# 14_LCD_Power_Supply.net
KiCad netlist of a schematic drawn in Altium Designer
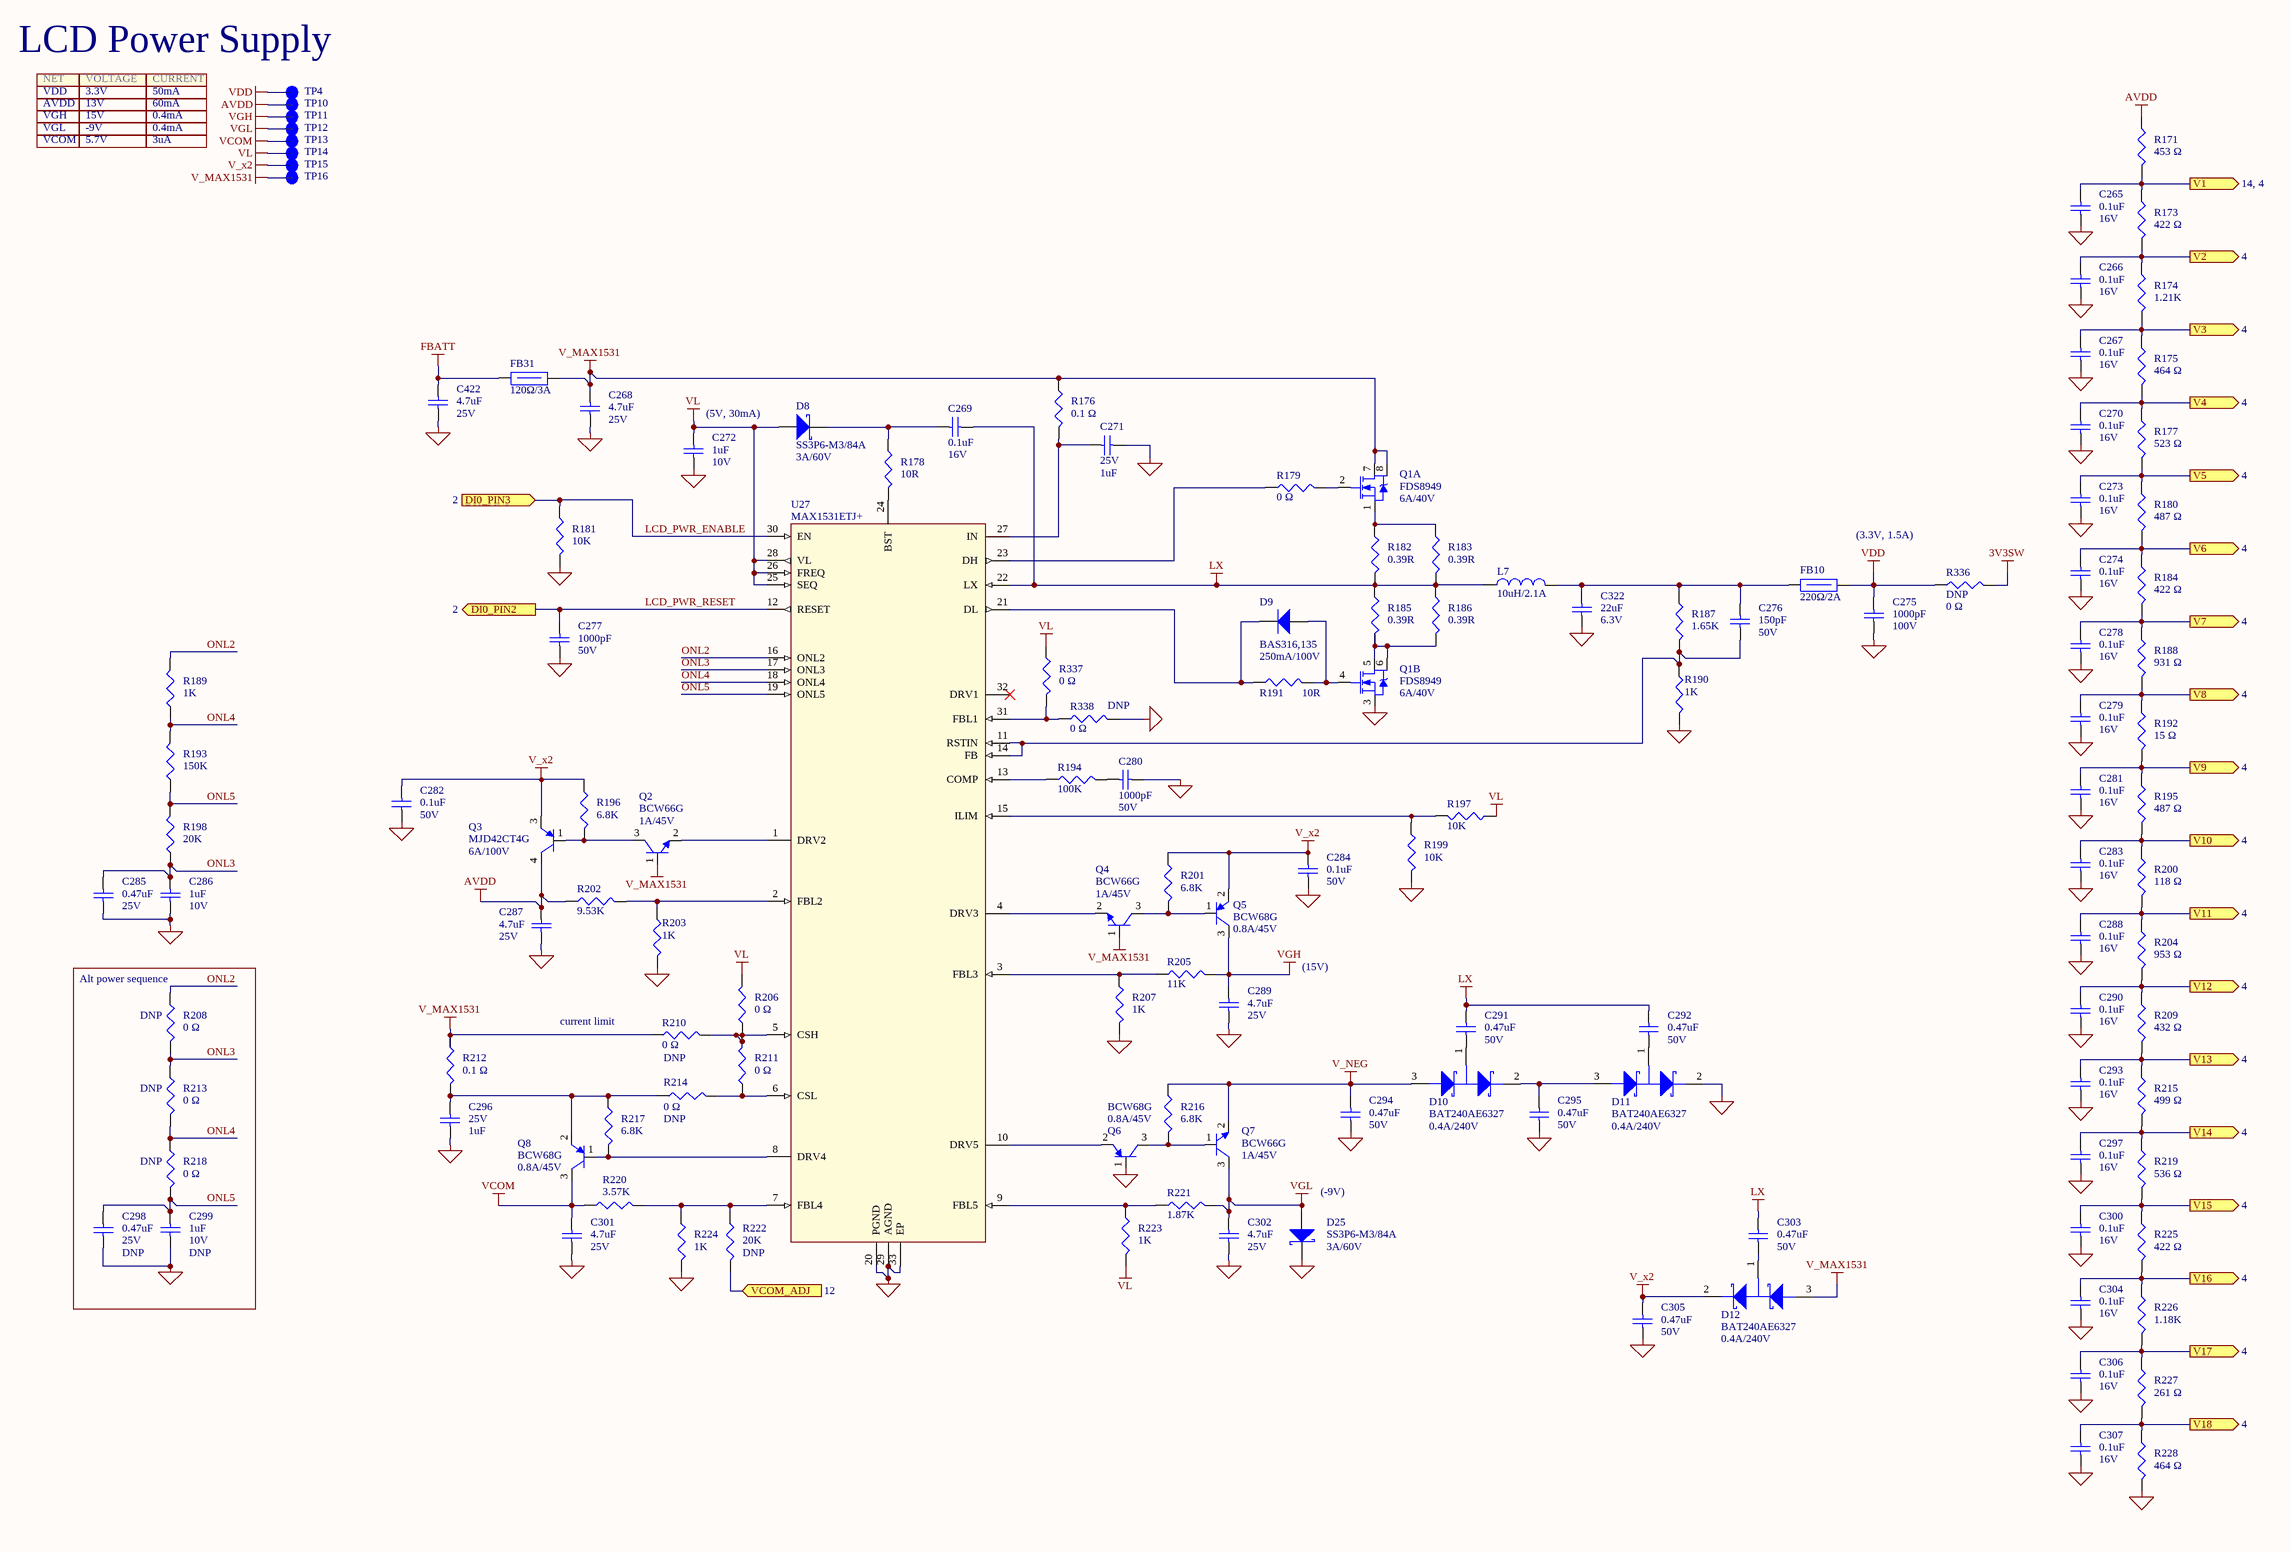
[diagram p0: 14 LCD Power Supply.SchDoc]

(export (version "E")
  (design (tool "Eeschema 10.0.6"))
  (components
    (comp (ref "C265")
      (value "0.1uF")
      (footprint "CAP_0402")
      (description "Cap, Cer, 0.1uF, 16V, 10%, X7R, 0402")
      (fields
        (field (name "TOLERANCE") "±10%")
        (field (name "MANUFACTURER") "Murata Electronics North America")
        (field (name "VOLTAGE") "16V")
      )
      (libsource (lib "Firstview") (part "Cap 0.1uF 16V 0402"))
    )
    (comp (ref "C266")
      (value "0.1uF")
      (footprint "CAP_0402")
      (description "Cap, Cer, 0.1uF, 16V, 10%, X7R, 0402")
      (fields
        (field (name "TOLERANCE") "±10%")
        (field (name "MANUFACTURER") "Murata Electronics North America")
        (field (name "VOLTAGE") "16V")
      )
      (libsource (lib "Firstview") (part "Cap 0.1uF 16V 0402"))
    )
    (comp (ref "C267")
      (value "0.1uF")
      (footprint "CAP_0402")
      (description "Cap, Cer, 0.1uF, 16V, 10%, X7R, 0402")
      (fields
        (field (name "TOLERANCE") "±10%")
        (field (name "MANUFACTURER") "Murata Electronics North America")
        (field (name "VOLTAGE") "16V")
      )
      (libsource (lib "Firstview") (part "Cap 0.1uF 16V 0402"))
    )
    (comp (ref "C268")
      (value "4.7uF")
      (footprint "CAP_0805")
      (description "Cap, Cer, 4.7uF, 25V, 10%, X5R, 0805")
      (fields
        (field (name "TOLERANCE") "10%")
        (field (name "MANUFACTURER") "Murata Electronics North America")
        (field (name "VOLTAGE") "25V")
      )
      (libsource (lib "Firstview") (part "Cap 4.7uF 25V 0805"))
    )
    (comp (ref "C269")
      (value "0.1uF")
      (footprint "CAP_0402")
      (description "Cap, Cer, 0.1uF, 16V, 10%, X7R, 0402")
      (fields
        (field (name "TOLERANCE") "±10%")
        (field (name "MANUFACTURER") "Murata Electronics North America")
        (field (name "VOLTAGE") "16V")
      )
      (libsource (lib "Firstview") (part "Cap 0.1uF 16V 0402"))
    )
    (comp (ref "C270")
      (value "0.1uF")
      (footprint "CAP_0402")
      (description "Cap, Cer, 0.1uF, 16V, 10%, X7R, 0402")
      (fields
        (field (name "TOLERANCE") "±10%")
        (field (name "MANUFACTURER") "Murata Electronics North America")
        (field (name "VOLTAGE") "16V")
      )
      (libsource (lib "Firstview") (part "Cap 0.1uF 16V 0402"))
    )
    (comp (ref "C271")
      (value "1uF")
      (footprint "CAP_0402")
      (description "Cap, Cer, 1uF, 25V, 10%, X5R, 0402")
      (fields
        (field (name "VOLTAGE") "25V")
        (field (name "MANUFACTURER") "Taiyo Yuden")
        (field (name "Comment") "Cap 1uF 25V 0402")
      )
      (libsource (lib "Firstview") (part "Cap 1uF 25V 0402"))
    )
    (comp (ref "C272")
      (value "1uF")
      (footprint "CAP_0402")
      (description "Cap, Cer, 1uF, 10V, ±10%, X5R, 0402")
      (fields
        (field (name "VOLTAGE") "10V")
        (field (name "MANUFACTURER") "Yageo")
        (field (name "Comment") "Cap 1uF 10V 0402")
      )
      (libsource (lib "Firstview") (part "Cap 1uF 10V 0402"))
    )
    (comp (ref "C273")
      (value "0.1uF")
      (footprint "CAP_0402")
      (description "Cap, Cer, 0.1uF, 16V, 10%, X7R, 0402")
      (fields
        (field (name "TOLERANCE") "±10%")
        (field (name "MANUFACTURER") "Murata Electronics North America")
        (field (name "VOLTAGE") "16V")
      )
      (libsource (lib "Firstview") (part "Cap 0.1uF 16V 0402"))
    )
    (comp (ref "C274")
      (value "0.1uF")
      (footprint "CAP_0402")
      (description "Cap, Cer, 0.1uF, 16V, 10%, X7R, 0402")
      (fields
        (field (name "TOLERANCE") "±10%")
        (field (name "MANUFACTURER") "Murata Electronics North America")
        (field (name "VOLTAGE") "16V")
      )
      (libsource (lib "Firstview") (part "Cap 0.1uF 16V 0402"))
    )
    (comp (ref "C275")
      (value "1000pF")
      (footprint "CAP_0402")
      (description "Cap, Cer, 1000pF, 100V, 20%, X7S, 0402")
      (fields
        (field (name "TOLERANCE") "20%")
        (field (name "MANUFACTURER") "TDK Corporation")
        (field (name "VOLTAGE") "100V")
      )
      (libsource (lib "Firstview") (part "Cap 1000pF 100V 0402"))
    )
    (comp (ref "C276")
      (value "150pF")
      (footprint "CAP_0402")
      (description "Cap, Cer, 150pF, 50V, 5%, C0G/NP0, 0603")
      (fields
        (field (name "TOLERANCE") "5%")
        (field (name "MANUFACTURER") "Samsung Electro-Mechanics America, Inc")
        (field (name "VOLTAGE") "50V")
      )
      (libsource (lib "Firstview") (part "Cap 150pF 50V 0603"))
    )
    (comp (ref "C277")
      (value "1000pF")
      (footprint "CAP_0603")
      (description "Cap, Cer, 1000pF, 50V, 10%, X7S, 0603")
      (fields
        (field (name "TOLERANCE") "10%")
        (field (name "MANUFACTURER") "Yageo")
        (field (name "VOLTAGE") "50V")
      )
      (libsource (lib "Firstview") (part "Cap 1000pF 50V 0603"))
    )
    (comp (ref "C278")
      (value "0.1uF")
      (footprint "CAP_0402")
      (description "Cap, Cer, 0.1uF, 16V, 10%, X7R, 0402")
      (fields
        (field (name "TOLERANCE") "±10%")
        (field (name "MANUFACTURER") "Murata Electronics North America")
        (field (name "VOLTAGE") "16V")
      )
      (libsource (lib "Firstview") (part "Cap 0.1uF 16V 0402"))
    )
    (comp (ref "C279")
      (value "0.1uF")
      (footprint "CAP_0402")
      (description "Cap, Cer, 0.1uF, 16V, 10%, X7R, 0402")
      (fields
        (field (name "TOLERANCE") "±10%")
        (field (name "MANUFACTURER") "Murata Electronics North America")
        (field (name "VOLTAGE") "16V")
      )
      (libsource (lib "Firstview") (part "Cap 0.1uF 16V 0402"))
    )
    (comp (ref "C280")
      (value "1000pF")
      (footprint "CAP_0603")
      (description "Cap, Cer, 1000pF, 50V, 10%, X7S, 0603")
      (fields
        (field (name "TOLERANCE") "10%")
        (field (name "MANUFACTURER") "Yageo")
        (field (name "VOLTAGE") "50V")
      )
      (libsource (lib "Firstview") (part "Cap 1000pF 50V 0603"))
    )
    (comp (ref "C281")
      (value "0.1uF")
      (footprint "CAP_0402")
      (description "Cap, Cer, 0.1uF, 16V, 10%, X7R, 0402")
      (fields
        (field (name "TOLERANCE") "±10%")
        (field (name "MANUFACTURER") "Murata Electronics North America")
        (field (name "VOLTAGE") "16V")
      )
      (libsource (lib "Firstview") (part "Cap 0.1uF 16V 0402"))
    )
    (comp (ref "C282")
      (value "0.1uF")
      (footprint "CAP_0402")
      (description "Cap, Cer, 0.1uF, 50V, 10%, X5R, 0402")
      (fields
        (field (name "TOLERANCE") "±10%")
        (field (name "MANUFACTURER") "TDK Corporation")
        (field (name "VOLTAGE") "50V")
      )
      (libsource (lib "Firstview") (part "Cap 0.1uF 50V 0402"))
    )
    (comp (ref "C283")
      (value "0.1uF")
      (footprint "CAP_0402")
      (description "Cap, Cer, 0.1uF, 16V, 10%, X7R, 0402")
      (fields
        (field (name "TOLERANCE") "±10%")
        (field (name "MANUFACTURER") "Murata Electronics North America")
        (field (name "VOLTAGE") "16V")
      )
      (libsource (lib "Firstview") (part "Cap 0.1uF 16V 0402"))
    )
    (comp (ref "C284")
      (value "0.1uF")
      (footprint "CAP_0402")
      (description "Cap, Cer, 0.1uF, 50V, 10%, X5R, 0402")
      (fields
        (field (name "TOLERANCE") "±10%")
        (field (name "MANUFACTURER") "TDK Corporation")
        (field (name "VOLTAGE") "50V")
      )
      (libsource (lib "Firstview") (part "Cap 0.1uF 50V 0402"))
    )
    (comp (ref "C285")
      (value "0.47uF")
      (footprint "CAP_0603")
      (description "Cap, Cer, 0.47uF, 25V, 10%, X7R, 0603")
      (fields
        (field (name "MANUFACTURER") "Samsung Electro-Mechanics America, Inc")
        (field (name "TOLERANCE") "10%")
        (field (name "VOLTAGE") "25V")
      )
      (libsource (lib "Firstview") (part "Cap 0.47uF 25V 0603"))
    )
    (comp (ref "C286")
      (value "1uF")
      (footprint "CAP_0402")
      (description "Cap, Cer, 1uF, 10V, ±10%, X5R, 0402")
      (fields
        (field (name "VOLTAGE") "10V")
        (field (name "MANUFACTURER") "Yageo")
        (field (name "Comment") "Cap 1uF 10V 0402")
      )
      (libsource (lib "Firstview") (part "Cap 1uF 10V 0402"))
    )
    (comp (ref "C287")
      (value "4.7uF")
      (footprint "CAP_0805")
      (description "Cap, Cer, 4.7uF, 25V, 10%, X5R, 0805")
      (fields
        (field (name "TOLERANCE") "10%")
        (field (name "MANUFACTURER") "Murata Electronics North America")
        (field (name "VOLTAGE") "25V")
      )
      (libsource (lib "Firstview") (part "Cap 4.7uF 25V 0805"))
    )
    (comp (ref "C288")
      (value "0.1uF")
      (footprint "CAP_0402")
      (description "Cap, Cer, 0.1uF, 16V, 10%, X7R, 0402")
      (fields
        (field (name "TOLERANCE") "±10%")
        (field (name "MANUFACTURER") "Murata Electronics North America")
        (field (name "VOLTAGE") "16V")
      )
      (libsource (lib "Firstview") (part "Cap 0.1uF 16V 0402"))
    )
    (comp (ref "C289")
      (value "4.7uF")
      (footprint "CAP_0805")
      (description "Cap, Cer, 4.7uF, 25V, 10%, X5R, 0805")
      (fields
        (field (name "TOLERANCE") "10%")
        (field (name "MANUFACTURER") "Murata Electronics North America")
        (field (name "VOLTAGE") "25V")
      )
      (libsource (lib "Firstview") (part "Cap 4.7uF 25V 0805"))
    )
    (comp (ref "C290")
      (value "0.1uF")
      (footprint "CAP_0402")
      (description "Cap, Cer, 0.1uF, 16V, 10%, X7R, 0402")
      (fields
        (field (name "TOLERANCE") "±10%")
        (field (name "MANUFACTURER") "Murata Electronics North America")
        (field (name "VOLTAGE") "16V")
      )
      (libsource (lib "Firstview") (part "Cap 0.1uF 16V 0402"))
    )
    (comp (ref "C291")
      (value "0.47uF")
      (footprint "CAP_1206")
      (description "Cap, Cer, 0.47uF, 50V, 10%, X7R, 1206")
      (fields
        (field (name "MANUFACTURER") "Yageo")
        (field (name "TOLERANCE") "10%")
        (field (name "VOLTAGE") "50V")
      )
      (libsource (lib "Firstview") (part "Cap 0.47uF 50V 1206"))
    )
    (comp (ref "C292")
      (value "0.47uF")
      (footprint "CAP_1206")
      (description "Cap, Cer, 0.47uF, 50V, 10%, X7R, 1206")
      (fields
        (field (name "MANUFACTURER") "Yageo")
        (field (name "TOLERANCE") "10%")
        (field (name "VOLTAGE") "50V")
      )
      (libsource (lib "Firstview") (part "Cap 0.47uF 50V 1206"))
    )
    (comp (ref "C293")
      (value "0.1uF")
      (footprint "CAP_0402")
      (description "Cap, Cer, 0.1uF, 16V, 10%, X7R, 0402")
      (fields
        (field (name "TOLERANCE") "±10%")
        (field (name "MANUFACTURER") "Murata Electronics North America")
        (field (name "VOLTAGE") "16V")
      )
      (libsource (lib "Firstview") (part "Cap 0.1uF 16V 0402"))
    )
    (comp (ref "C294")
      (value "0.47uF")
      (footprint "CAP_1206")
      (description "Cap, Cer, 0.47uF, 50V, 10%, X7R, 1206")
      (fields
        (field (name "MANUFACTURER") "Yageo")
        (field (name "TOLERANCE") "10%")
        (field (name "VOLTAGE") "50V")
      )
      (libsource (lib "Firstview") (part "Cap 0.47uF 50V 1206"))
    )
    (comp (ref "C295")
      (value "0.47uF")
      (footprint "CAP_1206")
      (description "Cap, Cer, 0.47uF, 50V, 10%, X7R, 1206")
      (fields
        (field (name "MANUFACTURER") "Yageo")
        (field (name "TOLERANCE") "10%")
        (field (name "VOLTAGE") "50V")
      )
      (libsource (lib "Firstview") (part "Cap 0.47uF 50V 1206"))
    )
    (comp (ref "C296")
      (value "1uF")
      (footprint "CAP_0402")
      (description "Cap, Cer, 1uF, 25V, 10%, X5R, 0402")
      (fields
        (field (name "VOLTAGE") "25V")
        (field (name "MANUFACTURER") "Taiyo Yuden")
        (field (name "Comment") "Cap 1uF 25V 0402")
      )
      (libsource (lib "Firstview") (part "Cap 1uF 25V 0402"))
    )
    (comp (ref "C297")
      (value "0.1uF")
      (footprint "CAP_0402")
      (description "Cap, Cer, 0.1uF, 16V, 10%, X7R, 0402")
      (fields
        (field (name "TOLERANCE") "±10%")
        (field (name "MANUFACTURER") "Murata Electronics North America")
        (field (name "VOLTAGE") "16V")
      )
      (libsource (lib "Firstview") (part "Cap 0.1uF 16V 0402"))
    )
    (comp (ref "C298")
      (value "0.47uF")
      (footprint "CAP_0603")
      (description "Cap, Cer, 0.47uF, 25V, 10%, X7R, 0603")
      (fields
        (field (name "MANUFACTURER") "Samsung Electro-Mechanics America, Inc")
        (field (name "TOLERANCE") "10%")
        (field (name "DNP") "DNP")
        (field (name "VOLTAGE") "25V")
      )
      (libsource (lib "Firstview") (part "Cap 0.47uF 25V 0603"))
    )
    (comp (ref "C299")
      (value "1uF")
      (footprint "CAP_0402")
      (description "Cap, Cer, 1uF, 10V, ±10%, X5R, 0402")
      (fields
        (field (name "DNP") "DNP")
        (field (name "VOLTAGE") "10V")
        (field (name "MANUFACTURER") "Yageo")
        (field (name "Comment") "Cap 1uF 10V 0402")
      )
      (libsource (lib "Firstview") (part "Cap 1uF 10V 0402"))
    )
    (comp (ref "C300")
      (value "0.1uF")
      (footprint "CAP_0402")
      (description "Cap, Cer, 0.1uF, 16V, 10%, X7R, 0402")
      (fields
        (field (name "TOLERANCE") "±10%")
        (field (name "MANUFACTURER") "Murata Electronics North America")
        (field (name "VOLTAGE") "16V")
      )
      (libsource (lib "Firstview") (part "Cap 0.1uF 16V 0402"))
    )
    (comp (ref "C301")
      (value "4.7uF")
      (footprint "CAP_0805")
      (description "Cap, Cer, 4.7uF, 25V, 10%, X5R, 0805")
      (fields
        (field (name "TOLERANCE") "10%")
        (field (name "MANUFACTURER") "Murata Electronics North America")
        (field (name "VOLTAGE") "25V")
      )
      (libsource (lib "Firstview") (part "Cap 4.7uF 25V 0805"))
    )
    (comp (ref "C302")
      (value "4.7uF")
      (footprint "CAP_0805")
      (description "Cap, Cer, 4.7uF, 25V, 10%, X5R, 0805")
      (fields
        (field (name "TOLERANCE") "10%")
        (field (name "MANUFACTURER") "Murata Electronics North America")
        (field (name "VOLTAGE") "25V")
      )
      (libsource (lib "Firstview") (part "Cap 4.7uF 25V 0805"))
    )
    (comp (ref "C303")
      (value "0.47uF")
      (footprint "CAP_1206")
      (description "Cap, Cer, 0.47uF, 50V, 10%, X7R, 1206")
      (fields
        (field (name "MANUFACTURER") "Yageo")
        (field (name "TOLERANCE") "10%")
        (field (name "VOLTAGE") "50V")
      )
      (libsource (lib "Firstview") (part "Cap 0.47uF 50V 1206"))
    )
    (comp (ref "C304")
      (value "0.1uF")
      (footprint "CAP_0402")
      (description "Cap, Cer, 0.1uF, 16V, 10%, X7R, 0402")
      (fields
        (field (name "TOLERANCE") "±10%")
        (field (name "MANUFACTURER") "Murata Electronics North America")
        (field (name "VOLTAGE") "16V")
      )
      (libsource (lib "Firstview") (part "Cap 0.1uF 16V 0402"))
    )
    (comp (ref "C305")
      (value "0.47uF")
      (footprint "CAP_1206")
      (description "Cap, Cer, 0.47uF, 50V, 10%, X7R, 1206")
      (fields
        (field (name "MANUFACTURER") "Yageo")
        (field (name "TOLERANCE") "10%")
        (field (name "VOLTAGE") "50V")
      )
      (libsource (lib "Firstview") (part "Cap 0.47uF 50V 1206"))
    )
    (comp (ref "C306")
      (value "0.1uF")
      (footprint "CAP_0402")
      (description "Cap, Cer, 0.1uF, 16V, 10%, X7R, 0402")
      (fields
        (field (name "TOLERANCE") "±10%")
        (field (name "MANUFACTURER") "Murata Electronics North America")
        (field (name "VOLTAGE") "16V")
      )
      (libsource (lib "Firstview") (part "Cap 0.1uF 16V 0402"))
    )
    (comp (ref "C307")
      (value "0.1uF")
      (footprint "CAP_0402")
      (description "Cap, Cer, 0.1uF, 16V, 10%, X7R, 0402")
      (fields
        (field (name "TOLERANCE") "±10%")
        (field (name "MANUFACTURER") "Murata Electronics North America")
        (field (name "VOLTAGE") "16V")
      )
      (libsource (lib "Firstview") (part "Cap 0.1uF 16V 0402"))
    )
    (comp (ref "C322")
      (value "22uF")
      (footprint "CAP_0805")
      (description "Cap, Cer, 22uF, 6.3V, 20%, X5R, 0805")
      (fields
        (field (name "TOLERANCE") "±20%")
        (field (name "MANUFACTURER") "Murata Electronics North America")
        (field (name "VOLTAGE") "6.3V")
      )
      (libsource (lib "Firstview") (part "Cap 22uF 6.3V 0805"))
    )
    (comp (ref "C422")
      (value "4.7uF")
      (footprint "CAP_0805")
      (description "Cap, Cer, 4.7uF, 25V, 10%, X5R, 0805")
      (fields
        (field (name "TOLERANCE") "10%")
        (field (name "MANUFACTURER") "Murata Electronics North America")
        (field (name "VOLTAGE") "25V")
      )
      (libsource (lib "Firstview") (part "Cap 4.7uF 25V 0805"))
    )
    (comp (ref "D8")
      (value "SS3P6-M3/84A")
      (footprint "DO-220AA_SS3P6-M3/84A")
      (description "Diode, Schottky, 3A, 60V, DO-220AA")
      (fields (field (name "MANUFACTURER") "Vishay") (field (name "ALTIUM_VALUE") "3A/60V"))
      (libsource (lib "Firstview") (part "SS3P6-M3/84A"))
    )
    (comp (ref "D9")
      (value "BAS316,135")
      (footprint "SOD-323-BAS316,135")
      (description "Diode, 250mA, 100V, SOD-323")
      (fields (field (name "MANUFACTURER") "NXP Semiconductors") (field (name "ALTIUM_VALUE") "250mA/100V"))
      (libsource (lib "Firstview") (part "BAS316,135"))
    )
    (comp (ref "D10")
      (value "BAT240AE6327")
      (footprint "SOT-23-3_BAT240AE6327")
      (description "Diode, Schottky, 0.4A, 240V, SOT-23-3")
      (fields (field (name "MANUFACTURER") "Infineon Technologies") (field (name "ALTIUM_VALUE") "0.4A/240V"))
      (libsource (lib "Firstview") (part "BAT240AE6327"))
    )
    (comp (ref "D11")
      (value "BAT240AE6327")
      (footprint "SOT-23-3_BAT240AE6327")
      (description "Diode, Schottky, 0.4A, 240V, SOT-23-3")
      (fields (field (name "MANUFACTURER") "Infineon Technologies") (field (name "ALTIUM_VALUE") "0.4A/240V"))
      (libsource (lib "Firstview") (part "BAT240AE6327"))
    )
    (comp (ref "D12")
      (value "BAT240AE6327")
      (footprint "SOT-23-3_BAT240AE6327")
      (description "Diode, Schottky, 0.4A, 240V, SOT-23-3")
      (fields (field (name "MANUFACTURER") "Infineon Technologies") (field (name "ALTIUM_VALUE") "0.4A/240V"))
      (libsource (lib "Firstview") (part "BAT240AE6327"))
    )
    (comp (ref "D25")
      (value "SS3P6-M3/84A")
      (footprint "DO-220AA_SS3P6-M3/84A")
      (description "Diode, Schottky, 3A, 60V, DO-220AA")
      (fields (field (name "MANUFACTURER") "Vishay") (field (name "ALTIUM_VALUE") "3A/60V"))
      (libsource (lib "Firstview") (part "SS3P6-M3/84A"))
    )
    (comp (ref "FB10")
      (value "220Ω/2A")
      (footprint "IND_0805")
      (description "Ind, Ferrite Bead, 220R, 50mOhm, 2A, 0805")
      (fields (field (name "MANUFACTURER") "Taiyo Yuden") (field (name "Comment") "BKP2125HS221-T"))
      (libsource (lib "Firstview") (part "BKP2125HS221-T"))
    )
    (comp (ref "FB31")
      (value "120Ω/3A")
      (footprint "IND_0603")
      (description "Ind, Ferrite Bead, 120R, 20mOhm, 3A, 0603")
      (fields
        (field (name "MANUFACTURER") "Murata Electronics North America")
        (field (name "Comment") "BLM18KG121TN1D")
      )
      (libsource (lib "Firstview") (part "BLM18KG121TN1D"))
    )
    (comp (ref "L7")
      (value "10uH/2.1A")
      (footprint "IND_2020")
      (description "Ind, Power, 10uH, 2.1A, 2020")
      (fields
        (field (name "TOLERANCE") "±20%")
        (field (name "MANUFACTURER") "Laird-Signal Integrity Products")
      )
      (libsource (lib "Firstview") (part "TYS5040100M-10"))
    )
    (comp (ref "Q1")
      (value "FDS8949")
      (footprint "SOIC-8_FDS8949")
      (description "Transistor, N-MOS, 6A, 40V, 29 mOhm, SOIC-8")
      (fields (field (name "MANUFACTURER") "Fairchild Semiconductor") (field (name "ALTIUM_VALUE") "6A/40V"))
      (libsource (lib "Firstview") (part "FDS8949"))
    )
    (comp (ref "Q2")
      (value "BCW66G")
      (footprint "SOT-23-3_BCW66G")
      (description "Transistor, NPN, 1A, 45V, SOT-23-3")
      (fields (field (name "MANUFACTURER") "Fairchild Semiconductor") (field (name "ALTIUM_VALUE") "1A/45V"))
      (libsource (lib "Firstview") (part "BCW66G"))
    )
    (comp (ref "Q3")
      (value "MJD42CT4G")
      (footprint "TO-252-3_MJD42CT4G")
      (description "Transistor, PNP, 6A, 100V, TO-252-3")
      (fields (field (name "MANUFACTURER") "ON Semiconductor") (field (name "ALTIUM_VALUE") "6A/100V"))
      (libsource (lib "Firstview") (part "MJD42CT4G"))
    )
    (comp (ref "Q4")
      (value "BCW66G")
      (footprint "SOT-23-3_BCW66G")
      (description "Transistor, NPN, 1A, 45V, SOT-23-3")
      (fields (field (name "MANUFACTURER") "Fairchild Semiconductor") (field (name "ALTIUM_VALUE") "1A/45V"))
      (libsource (lib "Firstview") (part "BCW66G"))
    )
    (comp (ref "Q5")
      (value "BCW68G")
      (footprint "SOT-23-3_BCW68G")
      (description "Transistor, PNP, 0.8A, 45V, SOT-23-3")
      (fields
        (field (name "MANUFACTURER") "Fairchild Semiconductor")
        (field (name "ALTIUM_VALUE") "0.8A/45V")
      )
      (libsource (lib "Firstview") (part "BCW68G"))
    )
    (comp (ref "Q6")
      (value "BCW68G")
      (footprint "SOT-23-3_BCW68G")
      (description "Transistor, PNP, 0.8A, 45V, SOT-23-3")
      (fields
        (field (name "MANUFACTURER") "Fairchild Semiconductor")
        (field (name "ALTIUM_VALUE") "0.8A/45V")
      )
      (libsource (lib "Firstview") (part "BCW68G"))
    )
    (comp (ref "Q7")
      (value "BCW66G")
      (footprint "SOT-23-3_BCW66G")
      (description "Transistor, NPN, 1A, 45V, SOT-23-3")
      (fields (field (name "MANUFACTURER") "Fairchild Semiconductor") (field (name "ALTIUM_VALUE") "1A/45V"))
      (libsource (lib "Firstview") (part "BCW66G"))
    )
    (comp (ref "Q8")
      (value "BCW68G")
      (footprint "SOT-23-3_BCW68G")
      (description "Transistor, PNP, 0.8A, 45V, SOT-23-3")
      (fields
        (field (name "MANUFACTURER") "Fairchild Semiconductor")
        (field (name "ALTIUM_VALUE") "0.8A/45V")
      )
      (libsource (lib "Firstview") (part "BCW68G"))
    )
    (comp (ref "R171")
      (value "453 Ω")
      (footprint "RES_0402")
      (description "Res, 453R, 0.063W, 1%, 0402")
      (fields
        (field (name "MANUFACTURER") "Stackpole Electronics Inc")
        (field (name "Comment") "Res 453R 0.063W")
      )
      (libsource (lib "Firstview") (part "Res 453R 0.063W"))
    )
    (comp (ref "R173")
      (value "422 Ω")
      (footprint "RES_0402")
      (description "Res, 442R, 0.063W, 1%, 0402")
      (fields
        (field (name "MANUFACTURER") "Stackpole Electronics Inc")
        (field (name "Comment") "Res 442R 0.063W")
      )
      (libsource (lib "Firstview") (part "Res 442R 0.063W"))
    )
    (comp (ref "R174")
      (value "1.21K")
      (footprint "RES_0402")
      (description "Res, 1.21K, 0.063W, 1%, 0402")
      (fields
        (field (name "MANUFACTURER") "Stackpole Electronics Inc")
        (field (name "Comment") "Res 1.21K 0.063W")
      )
      (libsource (lib "Firstview") (part "Res 1.21K 0.063W"))
    )
    (comp (ref "R175")
      (value "464 Ω")
      (footprint "RES_0402")
      (description "Res, 464R, 0.063W, 1%, 0402")
      (fields
        (field (name "MANUFACTURER") "Stackpole Electronics Inc")
        (field (name "Comment") "Res 464R 0.063W")
      )
      (libsource (lib "Firstview") (part "Res 464R 0.063W"))
    )
    (comp (ref "R176")
      (value "0.1 Ω")
      (footprint "RES_1206")
      (description "Res, 0.1 ohm, 1W, 1%, 1206")
      (fields
        (field (name "MANUFACTURER") "Samsung Electro-Mechanics America, Inc")
        (field (name "Comment") "Res 0.1 ohm 1W")
      )
      (libsource (lib "Firstview") (part "Res 0.1 ohm 1W"))
    )
    (comp (ref "R177")
      (value "523 Ω")
      (footprint "RES_0402")
      (description "Res, 523R, 0.063W, 1%, 0402")
      (fields
        (field (name "MANUFACTURER") "Stackpole Electronics Inc")
        (field (name "Comment") "Res 523R 0.063W")
      )
      (libsource (lib "Firstview") (part "Res 523R 0.063W"))
    )
    (comp (ref "R178")
      (value "10R")
      (footprint "RES_0402")
      (description "Res, 10R, 0.1W, 0402")
      (fields
        (field (name "MANUFACTURER") "Panasonic Electronic Components")
        (field (name "Comment") "Res 10R 0.1W")
      )
      (libsource (lib "Firstview") (part "Res 10R 0.1W"))
    )
    (comp (ref "R179")
      (value "0 Ω")
      (footprint "RES_0402")
      (description "Res, 0 ohm, 1/16W, 0402")
      (fields (field (name "MANUFACTURER") "Vishay Dale") (field (name "Comment") "Res 0 ohm 0.1W"))
      (libsource (lib "Firstview") (part "Res 0 ohm 0.1W"))
    )
    (comp (ref "R180")
      (value "487 Ω")
      (footprint "RES_0402")
      (description "Res, 467R, 0.063W, 1%, 0402")
      (fields
        (field (name "MANUFACTURER") "Stackpole Electronics Inc")
        (field (name "Comment") "Res 487R 0.063W")
      )
      (libsource (lib "Firstview") (part "Res 487R 0.063W"))
    )
    (comp (ref "R181")
      (value "10K")
      (footprint "RES_0402")
      (description "Res, 10K, 1/16W, 1%, 0402")
      (fields (field (name "MANUFACTURER") "Yageo") (field (name "Comment") "Res 10K 0.063W"))
      (libsource (lib "Firstview") (part "Res 10K 0.063W"))
    )
    (comp (ref "R182")
      (value "0.39R")
      (footprint "RES_0805")
      (description "Res, 0.39R, 0.25W, 1%, 0805")
      (fields
        (field (name "MANUFACTURER") "Samsung Electro-Mechanics America, Inc")
        (field (name "Comment") "Res 0.39R 0.25W")
      )
      (libsource (lib "Firstview") (part "Res 0.39R 0.25W"))
    )
    (comp (ref "R183")
      (value "0.39R")
      (footprint "RES_0805")
      (description "Res, 0.39R, 0.25W, 1%, 0805")
      (fields
        (field (name "MANUFACTURER") "Samsung Electro-Mechanics America, Inc")
        (field (name "Comment") "Res 0.39R 0.25W")
      )
      (libsource (lib "Firstview") (part "Res 0.39R 0.25W"))
    )
    (comp (ref "R184")
      (value "422 Ω")
      (footprint "RES_0402")
      (description "Res, 442R, 0.063W, 1%, 0402")
      (fields
        (field (name "MANUFACTURER") "Stackpole Electronics Inc")
        (field (name "Comment") "Res 442R 0.063W")
      )
      (libsource (lib "Firstview") (part "Res 442R 0.063W"))
    )
    (comp (ref "R185")
      (value "0.39R")
      (footprint "RES_0805")
      (description "Res, 0.39R, 0.25W, 1%, 0805")
      (fields
        (field (name "MANUFACTURER") "Samsung Electro-Mechanics America, Inc")
        (field (name "Comment") "Res 0.39R 0.25W")
      )
      (libsource (lib "Firstview") (part "Res 0.39R 0.25W"))
    )
    (comp (ref "R186")
      (value "0.39R")
      (footprint "RES_0805")
      (description "Res, 0.39R, 0.25W, 1%, 0805")
      (fields
        (field (name "MANUFACTURER") "Samsung Electro-Mechanics America, Inc")
        (field (name "Comment") "Res 0.39R 0.25W")
      )
      (libsource (lib "Firstview") (part "Res 0.39R 0.25W"))
    )
    (comp (ref "R187")
      (value "1.65K")
      (footprint "RES_0402")
      (description "Res, 1.65K, 0.1W, 1%, 0402")
      (fields (field (name "TOLERANCE") "1%") (field (name "MANUFACTURER") "Panasonic Electronic Components"))
      (libsource (lib "Firstview") (part "Res 1.65K 0.1W"))
    )
    (comp (ref "R188")
      (value "931 Ω")
      (footprint "RES_0402")
      (description "Res, 931R, 0.063W, 1%, 0402")
      (fields
        (field (name "MANUFACTURER") "Panasonic Electronic Components")
        (field (name "Comment") "Res 931R 0.063W")
      )
      (libsource (lib "Firstview") (part "Res 931R 0.063W"))
    )
    (comp (ref "R189")
      (value "1K")
      (footprint "RES_0402")
      (description "Res, 1K, 0.063W, 1%, 0402")
      (fields (field (name "TOLERANCE") "±1%") (field (name "MANUFACTURER") "Vishay Dale"))
      (libsource (lib "Firstview") (part "Res 1K 0.063W"))
    )
    (comp (ref "R190")
      (value "1K")
      (footprint "RES_0402")
      (description "Res, 1K, 0.063W, 1%, 0402")
      (fields (field (name "TOLERANCE") "±1%") (field (name "MANUFACTURER") "Vishay Dale"))
      (libsource (lib "Firstview") (part "Res 1K 0.063W"))
    )
    (comp (ref "R191")
      (value "10R")
      (footprint "RES_0402")
      (description "Res, 10R, 0.1W, 0402")
      (fields
        (field (name "MANUFACTURER") "Panasonic Electronic Components")
        (field (name "Comment") "Res 10R 0.1W")
      )
      (libsource (lib "Firstview") (part "Res 10R 0.1W"))
    )
    (comp (ref "R192")
      (value "15 Ω")
      (footprint "RES_0402")
      (description "Res, 15R, 0.063W, 1%, 0402")
      (fields
        (field (name "MANUFACTURER") "Stackpole Electronics Inc")
        (field (name "Comment") "Res 15R 0.063W")
      )
      (libsource (lib "Firstview") (part "Res 15R 0.063W"))
    )
    (comp (ref "R193")
      (value "150K")
      (footprint "RES_0402")
      (description "Res, 150K, 0.063W, 1%, 0402")
      (fields (field (name "TOLERANCE") "1%") (field (name "MANUFACTURER") "Rohm Semiconductor"))
      (libsource (lib "Firstview") (part "Res 150K 0.063W"))
    )
    (comp (ref "R194")
      (value "100K")
      (footprint "RES_0402")
      (description "Res, 100K, 0.1W, 1%, 0402")
      (fields
        (field (name "MANUFACTURER") "Panasonic Electronic Components")
        (field (name "Comment") "Res 100K 0.1W")
      )
      (libsource (lib "Firstview") (part "Res 100K 0.1W"))
    )
    (comp (ref "R195")
      (value "487 Ω")
      (footprint "RES_0402")
      (description "Res, 467R, 0.063W, 1%, 0402")
      (fields
        (field (name "MANUFACTURER") "Stackpole Electronics Inc")
        (field (name "Comment") "Res 487R 0.063W")
      )
      (libsource (lib "Firstview") (part "Res 487R 0.063W"))
    )
    (comp (ref "R196")
      (value "6.8K")
      (footprint "RES_0402")
      (description "Res, 6.8K, 0.1W, 1%, 0402")
      (fields
        (field (name "MANUFACTURER") "Panasonic Electronic Components")
        (field (name "Comment") "Res 6.8K 0.1W")
      )
      (libsource (lib "Firstview") (part "Res 6.8K 0.1W"))
    )
    (comp (ref "R197")
      (value "10K")
      (footprint "RES_0402")
      (description "Res, 10K, 1/16W, 1%, 0402")
      (fields (field (name "MANUFACTURER") "Yageo") (field (name "Comment") "Res 10K 0.063W"))
      (libsource (lib "Firstview") (part "Res 10K 0.063W"))
    )
    (comp (ref "R198")
      (value "20K")
      (footprint "RES_0402")
      (description "Res, 20K, 0.1W, 1%, 0402")
      (fields
        (field (name "MANUFACTURER") "Panasonic Electronic Components")
        (field (name "Comment") "Res 20K 0.1W")
      )
      (libsource (lib "Firstview") (part "Res 20K 0.1W"))
    )
    (comp (ref "R199")
      (value "10K")
      (footprint "RES_0402")
      (description "Res, 10K, 1/16W, 1%, 0402")
      (fields (field (name "MANUFACTURER") "Yageo") (field (name "Comment") "Res 10K 0.063W"))
      (libsource (lib "Firstview") (part "Res 10K 0.063W"))
    )
    (comp (ref "R200")
      (value "118 Ω")
      (footprint "RES_0402")
      (description "Res, 118R, 0.063W, 1%, 0402")
      (fields (field (name "MANUFACTURER") "Yageo") (field (name "Comment") "Res 118R 0.063W"))
      (libsource (lib "Firstview") (part "Res 118R 0.063W"))
    )
    (comp (ref "R201")
      (value "6.8K")
      (footprint "RES_0402")
      (description "Res, 6.8K, 0.1W, 1%, 0402")
      (fields
        (field (name "MANUFACTURER") "Panasonic Electronic Components")
        (field (name "Comment") "Res 6.8K 0.1W")
      )
      (libsource (lib "Firstview") (part "Res 6.8K 0.1W"))
    )
    (comp (ref "R202")
      (value "9.53K")
      (footprint "RES_0402")
      (description "Res, 9.53K, 0.063W, 1%, 0402")
      (fields (field (name "MANUFACTURER") "Yageo") (field (name "Comment") "Res 9.53K 0.063W"))
      (libsource (lib "Firstview") (part "Res 9.53K 0.063W"))
    )
    (comp (ref "R203")
      (value "1K")
      (footprint "RES_0402")
      (description "Res, 1K, 0.063W, 1%, 0402")
      (fields (field (name "TOLERANCE") "±1%") (field (name "MANUFACTURER") "Vishay Dale"))
      (libsource (lib "Firstview") (part "Res 1K 0.063W"))
    )
    (comp (ref "R204")
      (value "953 Ω")
      (footprint "RES_0402")
      (description "Res, 953R, 0.063W, 1%, 0402")
      (fields
        (field (name "MANUFACTURER") "Stackpole Electronics Inc")
        (field (name "Comment") "Res 953R 0.063W")
      )
      (libsource (lib "Firstview") (part "Res 953R 0.063W"))
    )
    (comp (ref "R205")
      (value "11K")
      (footprint "RES_0402")
      (description "Res, 11K, 0.1W, 1%, 0402")
      (fields
        (field (name "MANUFACTURER") "Panasonic Electronic Components")
        (field (name "Comment") "Res 11K 0.1W")
      )
      (libsource (lib "Firstview") (part "Res 11K 0.1W"))
    )
    (comp (ref "R206")
      (value "0 Ω")
      (footprint "RES_0402")
      (description "Res, 0 ohm, 1/16W, 0402")
      (fields (field (name "MANUFACTURER") "Vishay Dale") (field (name "Comment") "Res 0 ohm 0.1W"))
      (libsource (lib "Firstview") (part "Res 0 ohm 0.1W"))
    )
    (comp (ref "R207")
      (value "1K")
      (footprint "RES_0402")
      (description "Res, 1K, 0.063W, 1%, 0402")
      (fields (field (name "TOLERANCE") "±1%") (field (name "MANUFACTURER") "Vishay Dale"))
      (libsource (lib "Firstview") (part "Res 1K 0.063W"))
    )
    (comp (ref "R208")
      (value "0 Ω")
      (footprint "RES_0402")
      (description "Res, 0 ohm, 1/16W, 0402")
      (fields
        (field (name "DNP") "DNP")
        (field (name "MANUFACTURER") "Vishay Dale")
        (field (name "Comment") "Res 0 ohm 0.1W")
      )
      (libsource (lib "Firstview") (part "Res 0 ohm 0.1W"))
    )
    (comp (ref "R209")
      (value "432 Ω")
      (footprint "RES_0402")
      (description "Res, 432R, 0.063W, 1%, 0402")
      (fields
        (field (name "MANUFACTURER") "Stackpole Electronics Inc")
        (field (name "Comment") "Res 432R 0.063W")
      )
      (libsource (lib "Firstview") (part "Res 432R 0.063W"))
    )
    (comp (ref "R210")
      (value "0 Ω")
      (footprint "RES_0402")
      (description "Res, 0 ohm, 1/16W, 0402")
      (fields
        (field (name "DNP") "DNP")
        (field (name "MANUFACTURER") "Vishay Dale")
        (field (name "Comment") "Res 0 ohm 0.1W")
      )
      (libsource (lib "Firstview") (part "Res 0 ohm 0.1W"))
    )
    (comp (ref "R211")
      (value "0 Ω")
      (footprint "RES_0402")
      (description "Res, 0 ohm, 1/16W, 0402")
      (fields (field (name "MANUFACTURER") "Vishay Dale") (field (name "Comment") "Res 0 ohm 0.1W"))
      (libsource (lib "Firstview") (part "Res 0 ohm 0.1W"))
    )
    (comp (ref "R212")
      (value "0.1 Ω")
      (footprint "RES_1206")
      (description "Res, 0.1 ohm, 1W, 1%, 1206")
      (fields
        (field (name "MANUFACTURER") "Samsung Electro-Mechanics America, Inc")
        (field (name "Comment") "Res 0.1 ohm 1W")
      )
      (libsource (lib "Firstview") (part "Res 0.1 ohm 1W"))
    )
    (comp (ref "R213")
      (value "0 Ω")
      (footprint "RES_0402")
      (description "Res, 0 ohm, 1/16W, 0402")
      (fields
        (field (name "DNP") "DNP")
        (field (name "MANUFACTURER") "Vishay Dale")
        (field (name "Comment") "Res 0 ohm 0.1W")
      )
      (libsource (lib "Firstview") (part "Res 0 ohm 0.1W"))
    )
    (comp (ref "R214")
      (value "0 Ω")
      (footprint "RES_0402")
      (description "Res, 0 ohm, 1/16W, 0402")
      (fields
        (field (name "DNP") "DNP")
        (field (name "MANUFACTURER") "Vishay Dale")
        (field (name "Comment") "Res 0 ohm 0.1W")
      )
      (libsource (lib "Firstview") (part "Res 0 ohm 0.1W"))
    )
    (comp (ref "R215")
      (value "499 Ω")
      (footprint "RES_0402")
      (description "Res, 499R, 0.063W, 1%, 0402")
      (fields
        (field (name "MANUFACTURER") "Stackpole Electronics Inc")
        (field (name "Comment") "Res 499R 0.063W")
      )
      (libsource (lib "Firstview") (part "Res 499R 0.063W"))
    )
    (comp (ref "R216")
      (value "6.8K")
      (footprint "RES_0402")
      (description "Res, 6.8K, 0.1W, 1%, 0402")
      (fields
        (field (name "MANUFACTURER") "Panasonic Electronic Components")
        (field (name "Comment") "Res 6.8K 0.1W")
      )
      (libsource (lib "Firstview") (part "Res 6.8K 0.1W"))
    )
    (comp (ref "R217")
      (value "6.8K")
      (footprint "RES_0402")
      (description "Res, 6.8K, 0.1W, 1%, 0402")
      (fields
        (field (name "MANUFACTURER") "Panasonic Electronic Components")
        (field (name "Comment") "Res 6.8K 0.1W")
      )
      (libsource (lib "Firstview") (part "Res 6.8K 0.1W"))
    )
    (comp (ref "R218")
      (value "0 Ω")
      (footprint "RES_0402")
      (description "Res, 0 ohm, 1/16W, 0402")
      (fields
        (field (name "DNP") "DNP")
        (field (name "MANUFACTURER") "Vishay Dale")
        (field (name "Comment") "Res 0 ohm 0.1W")
      )
      (libsource (lib "Firstview") (part "Res 0 ohm 0.1W"))
    )
    (comp (ref "R219")
      (value "536 Ω")
      (footprint "RES_0402")
      (description "Res, 536R, 0.063W, 1%, 0402")
      (fields
        (field (name "MANUFACTURER") "Stackpole Electronics Inc")
        (field (name "Comment") "Res 536R 0.063W")
      )
      (libsource (lib "Firstview") (part "Res 536R 0.063W"))
    )
    (comp (ref "R220")
      (value "3.57K")
      (footprint "RES_0402")
      (description "Res, 3.57K, 0.1W, 1%, 0402")
      (fields
        (field (name "MANUFACTURER") "Panasonic Electronic Components")
        (field (name "Comment") "Res 3.57K 0.1W")
      )
      (libsource (lib "Firstview") (part "Res 3.57K 0.1W"))
    )
    (comp (ref "R221")
      (value "1.87K")
      (footprint "RES_0402")
      (description "Res, 1.87K, 0.063W, 1%, 0402")
      (fields (field (name "TOLERANCE") "1%") (field (name "MANUFACTURER") "Stackpole Electronics Inc"))
      (libsource (lib "Firstview") (part "Res 1.87K 0.063W"))
    )
    (comp (ref "R222")
      (value "20K")
      (footprint "RES_0402")
      (description "Res, 20K, 0.1W, 1%, 0402")
      (fields
        (field (name "DNP") "DNP")
        (field (name "MANUFACTURER") "Panasonic Electronic Components")
        (field (name "Comment") "Res 20K 0.1W")
      )
      (libsource (lib "Firstview") (part "Res 20K 0.1W"))
    )
    (comp (ref "R223")
      (value "1K")
      (footprint "RES_0402")
      (description "Res, 1K, 0.063W, 1%, 0402")
      (fields (field (name "TOLERANCE") "±1%") (field (name "MANUFACTURER") "Vishay Dale"))
      (libsource (lib "Firstview") (part "Res 1K 0.063W"))
    )
    (comp (ref "R224")
      (value "1K")
      (footprint "RES_0402")
      (description "Res, 1K, 0.063W, 1%, 0402")
      (fields (field (name "TOLERANCE") "±1%") (field (name "MANUFACTURER") "Vishay Dale"))
      (libsource (lib "Firstview") (part "Res 1K 0.063W"))
    )
    (comp (ref "R225")
      (value "422 Ω")
      (footprint "RES_0402")
      (description "Res, 442R, 0.063W, 1%, 0402")
      (fields
        (field (name "MANUFACTURER") "Stackpole Electronics Inc")
        (field (name "Comment") "Res 442R 0.063W")
      )
      (libsource (lib "Firstview") (part "Res 442R 0.063W"))
    )
    (comp (ref "R226")
      (value "1.18K")
      (footprint "RES_0402")
      (description "Res, 1.18K, 0.063W, 1%, 0402")
      (fields
        (field (name "MANUFACTURER") "Stackpole Electronics Inc")
        (field (name "Comment") "Res 1.18K 0.063W")
      )
      (libsource (lib "Firstview") (part "Res 1.18K 0.063W"))
    )
    (comp (ref "R227")
      (value "261 Ω")
      (footprint "RES_0402")
      (description "Res, 261R, 0.063W, 1%, 0402")
      (fields (field (name "TOLERANCE") "1%") (field (name "MANUFACTURER") "Stackpole Electronics Inc"))
      (libsource (lib "Firstview") (part "Res 261R 0.063W"))
    )
    (comp (ref "R228")
      (value "464 Ω")
      (footprint "RES_0402")
      (description "Res, 464R, 0.063W, 1%, 0402")
      (fields
        (field (name "MANUFACTURER") "Stackpole Electronics Inc")
        (field (name "Comment") "Res 464R 0.063W")
      )
      (libsource (lib "Firstview") (part "Res 464R 0.063W"))
    )
    (comp (ref "R336")
      (value "0 Ω")
      (footprint "RES_0402")
      (description "Res, 0 ohm, 1/16W, 0402")
      (fields
        (field (name "MANUFACTURER") "Vishay Dale")
        (field (name "DNP") "DNP")
        (field (name "Comment") "Res 0 ohm 0.1W DNP")
      )
      (libsource (lib "Firstview") (part "Res 0 ohm 0.1W DNP"))
    )
    (comp (ref "R337")
      (value "0 Ω")
      (footprint "RES_0402")
      (description "Res, 0 ohm, 1/16W, 0402")
      (fields (field (name "MANUFACTURER") "Vishay Dale") (field (name "Comment") "Res 0 ohm 0.1W"))
      (libsource (lib "Firstview") (part "Res 0 ohm 0.1W"))
    )
    (comp (ref "R338")
      (value "0 Ω")
      (footprint "RES_0402")
      (description "Res, 0 ohm, 1/16W, 0402")
      (fields
        (field (name "DNP") "DNP")
        (field (name "MANUFACTURER") "Vishay Dale")
        (field (name "Comment") "Res 0 ohm 0.1W")
      )
      (libsource (lib "Firstview") (part "Res 0 ohm 0.1W"))
    )
    (comp (ref "TP4")
      (value "TP")
      (footprint "TP_TH_12_20")
      (description "Testpad")
      (libsource (lib "Firstview") (part "TestPoint"))
    )
    (comp (ref "TP10")
      (value "TP")
      (footprint "TP_TH_12_20")
      (description "Testpad")
      (libsource (lib "Firstview") (part "TestPoint"))
    )
    (comp (ref "TP11")
      (value "TP")
      (footprint "TP_TH_12_20")
      (description "Testpad")
      (libsource (lib "Firstview") (part "TestPoint"))
    )
    (comp (ref "TP12")
      (value "TP")
      (footprint "TP_TH_12_20")
      (description "Testpad")
      (libsource (lib "Firstview") (part "TestPoint"))
    )
    (comp (ref "TP13")
      (value "TP")
      (footprint "TP_TH_12_20")
      (description "Testpad")
      (libsource (lib "Firstview") (part "TestPoint"))
    )
    (comp (ref "TP14")
      (value "TP")
      (footprint "TP_TH_12_20")
      (description "Testpad")
      (libsource (lib "Firstview") (part "TestPoint"))
    )
    (comp (ref "TP15")
      (value "TP")
      (footprint "TP_TH_12_20")
      (description "Testpad")
      (libsource (lib "Firstview") (part "TestPoint"))
    )
    (comp (ref "TP16")
      (value "TP")
      (footprint "TP_TH_12_20")
      (description "Testpad")
      (libsource (lib "Firstview") (part "TestPoint"))
    )
    (comp (ref "U27")
      (value "MAX1531ETJ+")
      (footprint "TQFN-32_MAX1531ETJ+")
      (description "IC, LCD Power, 4.5-28V, TQFN-32")
      (fields (field (name "MANUFACTURER") "Maxim Integrated"))
      (libsource (lib "Firstview") (part "MAX1531ETJ+"))
    )
  )
  (nets
    (net (code "1") (name "/LCD_PWR_ENABLE") (class "Default")
      (node (ref "R181") (pin "1") (pinfunction "1_1") (pintype "passive"))
      (node (ref "U27") (pin "30") (pinfunction "EN_30") (pintype "input"))
    )
    (net (code "2") (name "/LCD_PWR_RESET") (class "Default")
      (node (ref "C277") (pin "1") (pinfunction "1_1") (pintype "passive"))
      (node (ref "U27") (pin "12") (pinfunction "RESET_12") (pintype "output"))
    )
    (net (code "3") (name "/ONL2") (class "Default")
      (node (ref "R189") (pin "2") (pinfunction "2_2") (pintype "passive"))
      (node (ref "R208") (pin "1") (pinfunction "1_1") (pintype "passive"))
      (node (ref "U27") (pin "16") (pinfunction "ONL2_16") (pintype "input"))
    )
    (net (code "4") (name "/ONL3") (class "Default")
      (node (ref "C285") (pin "1") (pinfunction "1_1") (pintype "passive"))
      (node (ref "C286") (pin "1") (pinfunction "1_1") (pintype "passive"))
      (node (ref "R198") (pin "1") (pinfunction "1_1") (pintype "passive"))
      (node (ref "R208") (pin "2") (pinfunction "2_2") (pintype "passive"))
      (node (ref "R213") (pin "1") (pinfunction "1_1") (pintype "passive"))
      (node (ref "U27") (pin "17") (pinfunction "ONL3_17") (pintype "input"))
    )
    (net (code "5") (name "/ONL4") (class "Default")
      (node (ref "R189") (pin "1") (pinfunction "1_1") (pintype "passive"))
      (node (ref "R193") (pin "2") (pinfunction "2_2") (pintype "passive"))
      (node (ref "R213") (pin "2") (pinfunction "2_2") (pintype "passive"))
      (node (ref "R218") (pin "1") (pinfunction "1_1") (pintype "passive"))
      (node (ref "U27") (pin "18") (pinfunction "ONL4_18") (pintype "input"))
    )
    (net (code "6") (name "/ONL5") (class "Default")
      (node (ref "C298") (pin "1") (pinfunction "1_1") (pintype "passive"))
      (node (ref "C299") (pin "1") (pinfunction "1_1") (pintype "passive"))
      (node (ref "R193") (pin "1") (pinfunction "1_1") (pintype "passive"))
      (node (ref "R198") (pin "2") (pinfunction "2_2") (pintype "passive"))
      (node (ref "R218") (pin "2") (pinfunction "2_2") (pintype "passive"))
      (node (ref "U27") (pin "19") (pinfunction "ONL5_19") (pintype "input"))
    )
    (net (code "7") (name "/V1") (class "Default")
      (node (ref "C265") (pin "1") (pinfunction "1_1") (pintype "passive"))
      (node (ref "R171") (pin "2") (pinfunction "2_2") (pintype "passive"))
      (node (ref "R173") (pin "1") (pinfunction "1_1") (pintype "passive"))
    )
    (net (code "8") (name "/V2") (class "Default")
      (node (ref "C266") (pin "1") (pinfunction "1_1") (pintype "passive"))
      (node (ref "R173") (pin "2") (pinfunction "2_2") (pintype "passive"))
      (node (ref "R174") (pin "1") (pinfunction "1_1") (pintype "passive"))
    )
    (net (code "9") (name "/V3") (class "Default")
      (node (ref "C267") (pin "1") (pinfunction "1_1") (pintype "passive"))
      (node (ref "R174") (pin "2") (pinfunction "2_2") (pintype "passive"))
      (node (ref "R175") (pin "1") (pinfunction "1_1") (pintype "passive"))
    )
    (net (code "10") (name "/V4") (class "Default")
      (node (ref "C270") (pin "1") (pinfunction "1_1") (pintype "passive"))
      (node (ref "R175") (pin "2") (pinfunction "2_2") (pintype "passive"))
      (node (ref "R177") (pin "1") (pinfunction "1_1") (pintype "passive"))
    )
    (net (code "11") (name "/V5") (class "Default")
      (node (ref "C273") (pin "1") (pinfunction "1_1") (pintype "passive"))
      (node (ref "R177") (pin "2") (pinfunction "2_2") (pintype "passive"))
      (node (ref "R180") (pin "1") (pinfunction "1_1") (pintype "passive"))
    )
    (net (code "12") (name "/V6") (class "Default")
      (node (ref "C274") (pin "1") (pinfunction "1_1") (pintype "passive"))
      (node (ref "R180") (pin "2") (pinfunction "2_2") (pintype "passive"))
      (node (ref "R184") (pin "1") (pinfunction "1_1") (pintype "passive"))
    )
    (net (code "13") (name "/V7") (class "Default")
      (node (ref "C278") (pin "1") (pinfunction "1_1") (pintype "passive"))
      (node (ref "R184") (pin "2") (pinfunction "2_2") (pintype "passive"))
      (node (ref "R188") (pin "1") (pinfunction "1_1") (pintype "passive"))
    )
    (net (code "14") (name "/V8") (class "Default")
      (node (ref "C279") (pin "1") (pinfunction "1_1") (pintype "passive"))
      (node (ref "R188") (pin "2") (pinfunction "2_2") (pintype "passive"))
      (node (ref "R192") (pin "1") (pinfunction "1_1") (pintype "passive"))
    )
    (net (code "15") (name "/V9") (class "Default")
      (node (ref "C281") (pin "1") (pinfunction "1_1") (pintype "passive"))
      (node (ref "R192") (pin "2") (pinfunction "2_2") (pintype "passive"))
      (node (ref "R195") (pin "1") (pinfunction "1_1") (pintype "passive"))
    )
    (net (code "16") (name "/V10") (class "Default")
      (node (ref "C283") (pin "1") (pinfunction "1_1") (pintype "passive"))
      (node (ref "R195") (pin "2") (pinfunction "2_2") (pintype "passive"))
      (node (ref "R200") (pin "1") (pinfunction "1_1") (pintype "passive"))
    )
    (net (code "17") (name "/V11") (class "Default")
      (node (ref "C288") (pin "1") (pinfunction "1_1") (pintype "passive"))
      (node (ref "R200") (pin "2") (pinfunction "2_2") (pintype "passive"))
      (node (ref "R204") (pin "1") (pinfunction "1_1") (pintype "passive"))
    )
    (net (code "18") (name "/V12") (class "Default")
      (node (ref "C290") (pin "1") (pinfunction "1_1") (pintype "passive"))
      (node (ref "R204") (pin "2") (pinfunction "2_2") (pintype "passive"))
      (node (ref "R209") (pin "1") (pinfunction "1_1") (pintype "passive"))
    )
    (net (code "19") (name "/V13") (class "Default")
      (node (ref "C293") (pin "1") (pinfunction "1_1") (pintype "passive"))
      (node (ref "R209") (pin "2") (pinfunction "2_2") (pintype "passive"))
      (node (ref "R215") (pin "1") (pinfunction "1_1") (pintype "passive"))
    )
    (net (code "20") (name "/V14") (class "Default")
      (node (ref "C297") (pin "1") (pinfunction "1_1") (pintype "passive"))
      (node (ref "R215") (pin "2") (pinfunction "2_2") (pintype "passive"))
      (node (ref "R219") (pin "1") (pinfunction "1_1") (pintype "passive"))
    )
    (net (code "21") (name "/V15") (class "Default")
      (node (ref "C300") (pin "1") (pinfunction "1_1") (pintype "passive"))
      (node (ref "R219") (pin "2") (pinfunction "2_2") (pintype "passive"))
      (node (ref "R225") (pin "1") (pinfunction "1_1") (pintype "passive"))
    )
    (net (code "22") (name "/V16") (class "Default")
      (node (ref "C304") (pin "1") (pinfunction "1_1") (pintype "passive"))
      (node (ref "R225") (pin "2") (pinfunction "2_2") (pintype "passive"))
      (node (ref "R226") (pin "1") (pinfunction "1_1") (pintype "passive"))
    )
    (net (code "23") (name "/V17") (class "Default")
      (node (ref "C306") (pin "1") (pinfunction "1_1") (pintype "passive"))
      (node (ref "R226") (pin "2") (pinfunction "2_2") (pintype "passive"))
      (node (ref "R227") (pin "1") (pinfunction "1_1") (pintype "passive"))
    )
    (net (code "24") (name "/V18") (class "Default")
      (node (ref "C307") (pin "1") (pinfunction "1_1") (pintype "passive"))
      (node (ref "R227") (pin "2") (pinfunction "2_2") (pintype "passive"))
      (node (ref "R228") (pin "1") (pinfunction "1_1") (pintype "passive"))
    )
    (net (code "25") (name "/VCOM_ADJ") (class "Default")
      (node (ref "R222") (pin "2") (pinfunction "2_2") (pintype "passive"))
    )
    (net (code "26") (name "3V3SW") (class "Default")
      (node (ref "R336") (pin "2") (pinfunction "2_2") (pintype "passive"))
    )
    (net (code "27") (name "AVDD") (class "Default")
      (node (ref "C287") (pin "1") (pinfunction "1_1") (pintype "passive"))
      (node (ref "Q3") (pin "4") (pinfunction "C_4") (pintype "passive"))
      (node (ref "R171") (pin "1") (pinfunction "1_1") (pintype "passive"))
      (node (ref "R202") (pin "1") (pinfunction "1_1") (pintype "passive"))
      (node (ref "TP10") (pin "1") (pinfunction "1_1") (pintype "passive"))
    )
    (net (code "28") (name "FBATT") (class "Default")
      (node (ref "C422") (pin "1") (pinfunction "1_1") (pintype "passive"))
      (node (ref "FB31") (pin "1") (pinfunction "1_1") (pintype "passive"))
    )
    (net (code "29") (name "GND") (class "Default")
      (node (ref "C265") (pin "2") (pinfunction "2_2") (pintype "passive"))
      (node (ref "C266") (pin "2") (pinfunction "2_2") (pintype "passive"))
      (node (ref "C267") (pin "2") (pinfunction "2_2") (pintype "passive"))
      (node (ref "C268") (pin "2") (pinfunction "2_2") (pintype "passive"))
      (node (ref "C270") (pin "2") (pinfunction "2_2") (pintype "passive"))
      (node (ref "C271") (pin "2") (pinfunction "2_2") (pintype "passive"))
      (node (ref "C272") (pin "2") (pinfunction "2_2") (pintype "passive"))
      (node (ref "C273") (pin "2") (pinfunction "2_2") (pintype "passive"))
      (node (ref "C274") (pin "2") (pinfunction "2_2") (pintype "passive"))
      (node (ref "C275") (pin "2") (pinfunction "2_2") (pintype "passive"))
      (node (ref "C277") (pin "2") (pinfunction "2_2") (pintype "passive"))
      (node (ref "C278") (pin "2") (pinfunction "2_2") (pintype "passive"))
      (node (ref "C279") (pin "2") (pinfunction "2_2") (pintype "passive"))
      (node (ref "C280") (pin "2") (pinfunction "2_2") (pintype "passive"))
      (node (ref "C281") (pin "2") (pinfunction "2_2") (pintype "passive"))
      (node (ref "C282") (pin "2") (pinfunction "2_2") (pintype "passive"))
      (node (ref "C283") (pin "2") (pinfunction "2_2") (pintype "passive"))
      (node (ref "C284") (pin "2") (pinfunction "2_2") (pintype "passive"))
      (node (ref "C285") (pin "2") (pinfunction "2_2") (pintype "passive"))
      (node (ref "C286") (pin "2") (pinfunction "2_2") (pintype "passive"))
      (node (ref "C287") (pin "2") (pinfunction "2_2") (pintype "passive"))
      (node (ref "C288") (pin "2") (pinfunction "2_2") (pintype "passive"))
      (node (ref "C289") (pin "2") (pinfunction "2_2") (pintype "passive"))
      (node (ref "C290") (pin "2") (pinfunction "2_2") (pintype "passive"))
      (node (ref "C293") (pin "2") (pinfunction "2_2") (pintype "passive"))
      (node (ref "C294") (pin "2") (pinfunction "2_2") (pintype "passive"))
      (node (ref "C295") (pin "2") (pinfunction "2_2") (pintype "passive"))
      (node (ref "C296") (pin "2") (pinfunction "2_2") (pintype "passive"))
      (node (ref "C297") (pin "2") (pinfunction "2_2") (pintype "passive"))
      (node (ref "C298") (pin "2") (pinfunction "2_2") (pintype "passive"))
      (node (ref "C299") (pin "2") (pinfunction "2_2") (pintype "passive"))
      (node (ref "C300") (pin "2") (pinfunction "2_2") (pintype "passive"))
      (node (ref "C301") (pin "2") (pinfunction "2_2") (pintype "passive"))
      (node (ref "C302") (pin "2") (pinfunction "2_2") (pintype "passive"))
      (node (ref "C304") (pin "2") (pinfunction "2_2") (pintype "passive"))
      (node (ref "C305") (pin "2") (pinfunction "2_2") (pintype "passive"))
      (node (ref "C306") (pin "2") (pinfunction "2_2") (pintype "passive"))
      (node (ref "C307") (pin "2") (pinfunction "2_2") (pintype "passive"))
      (node (ref "C322") (pin "2") (pinfunction "2_2") (pintype "passive"))
      (node (ref "C422") (pin "2") (pinfunction "2_2") (pintype "passive"))
      (node (ref "D11") (pin "2") (pinfunction "K2_2") (pintype "passive"))
      (node (ref "D25") (pin "K") (pinfunction "K_K") (pintype "passive"))
      (node (ref "Q1") (pin "3") (pinfunction "S2_3") (pintype "passive"))
      (node (ref "Q6") (pin "1") (pinfunction "B_1") (pintype "passive"))
      (node (ref "R181") (pin "2") (pinfunction "2_2") (pintype "passive"))
      (node (ref "R190") (pin "2") (pinfunction "2_2") (pintype "passive"))
      (node (ref "R199") (pin "2") (pinfunction "2_2") (pintype "passive"))
      (node (ref "R203") (pin "2") (pinfunction "2_2") (pintype "passive"))
      (node (ref "R207") (pin "2") (pinfunction "2_2") (pintype "passive"))
      (node (ref "R224") (pin "2") (pinfunction "2_2") (pintype "passive"))
      (node (ref "R228") (pin "2") (pinfunction "2_2") (pintype "passive"))
      (node (ref "R338") (pin "2") (pinfunction "2_2") (pintype "passive"))
      (node (ref "U27") (pin "20") (pinfunction "PGND_20") (pintype "power_in"))
      (node (ref "U27") (pin "29") (pinfunction "AGND_29") (pintype "power_in"))
      (node (ref "U27") (pin "33") (pinfunction "EP_33") (pintype "power_in"))
    )
    (net (code "30") (name "LX") (class "Default")
      (node (ref "C269") (pin "2") (pinfunction "2_2") (pintype "passive"))
      (node (ref "C291") (pin "2") (pinfunction "2_2") (pintype "passive"))
      (node (ref "C292") (pin "2") (pinfunction "2_2") (pintype "passive"))
      (node (ref "C303") (pin "1") (pinfunction "1_1") (pintype "passive"))
      (node (ref "L7") (pin "1") (pinfunction "1_1") (pintype "passive"))
      (node (ref "R182") (pin "2") (pinfunction "2_2") (pintype "passive"))
      (node (ref "R183") (pin "2") (pinfunction "2_2") (pintype "passive"))
      (node (ref "R185") (pin "1") (pinfunction "1_1") (pintype "passive"))
      (node (ref "R186") (pin "1") (pinfunction "1_1") (pintype "passive"))
      (node (ref "U27") (pin "22") (pinfunction "LX_22") (pintype "input"))
    )
    (net (code "31") (name "Net-(C269-Pad1)") (class "Default")
      (node (ref "C269") (pin "1") (pinfunction "1_1") (pintype "passive"))
      (node (ref "D8") (pin "K") (pinfunction "K_K") (pintype "passive"))
      (node (ref "R178") (pin "1") (pinfunction "1_1") (pintype "passive"))
    )
    (net (code "32") (name "Net-(C276-Pad1)") (class "Default")
      (node (ref "C276") (pin "1") (pinfunction "1_1") (pintype "passive"))
      (node (ref "C322") (pin "1") (pinfunction "1_1") (pintype "passive"))
      (node (ref "FB10") (pin "1") (pinfunction "1_1") (pintype "passive"))
      (node (ref "L7") (pin "2") (pinfunction "2_2") (pintype "passive"))
      (node (ref "R187") (pin "1") (pinfunction "1_1") (pintype "passive"))
    )
    (net (code "33") (name "Net-(C280-Pad1)") (class "Default")
      (node (ref "C280") (pin "1") (pinfunction "1_1") (pintype "passive"))
      (node (ref "R194") (pin "2") (pinfunction "2_2") (pintype "passive"))
    )
    (net (code "34") (name "Net-(C291-Pad1)") (class "Default")
      (node (ref "C291") (pin "1") (pinfunction "1_1") (pintype "passive"))
      (node (ref "D10") (pin "1") (pinfunction "1_1") (pintype "passive"))
    )
    (net (code "35") (name "Net-(C292-Pad1)") (class "Default")
      (node (ref "C292") (pin "1") (pinfunction "1_1") (pintype "passive"))
      (node (ref "D11") (pin "1") (pinfunction "1_1") (pintype "passive"))
    )
    (net (code "36") (name "Net-(C303-Pad2)") (class "Default")
      (node (ref "C303") (pin "2") (pinfunction "2_2") (pintype "passive"))
      (node (ref "D12") (pin "1") (pinfunction "1_1") (pintype "passive"))
    )
    (net (code "37") (name "Net-(D10-K2)") (class "Default")
      (node (ref "C295") (pin "1") (pinfunction "1_1") (pintype "passive"))
      (node (ref "D10") (pin "2") (pinfunction "K2_2") (pintype "passive"))
      (node (ref "D11") (pin "3") (pinfunction "A1_3") (pintype "passive"))
    )
    (net (code "38") (name "Net-(Q1A-G1)") (class "Default")
      (node (ref "Q1") (pin "2") (pinfunction "G1_2") (pintype "passive"))
      (node (ref "R179") (pin "2") (pinfunction "2_2") (pintype "passive"))
    )
    (net (code "39") (name "Net-(Q1A-S1)") (class "Default")
      (node (ref "Q1") (pin "1") (pinfunction "S1_1") (pintype "passive"))
      (node (ref "R182") (pin "1") (pinfunction "1_1") (pintype "passive"))
      (node (ref "R183") (pin "1") (pinfunction "1_1") (pintype "passive"))
    )
    (net (code "40") (name "Net-(Q1B-D2-Pad5)") (class "Default")
      (node (ref "Q1") (pin "5") (pinfunction "D2_5") (pintype "passive"))
      (node (ref "Q1") (pin "6") (pinfunction "D2_6") (pintype "passive"))
      (node (ref "R185") (pin "2") (pinfunction "2_2") (pintype "passive"))
      (node (ref "R186") (pin "2") (pinfunction "2_2") (pintype "passive"))
    )
    (net (code "41") (name "Net-(Q1B-G2)") (class "Default")
      (node (ref "D9") (pin "A") (pinfunction "A_A") (pintype "passive"))
      (node (ref "Q1") (pin "4") (pinfunction "G2_4") (pintype "passive"))
      (node (ref "R191") (pin "2") (pinfunction "2_2") (pintype "passive"))
    )
    (net (code "42") (name "Net-(Q2-C)") (class "Default")
      (node (ref "Q2") (pin "3") (pinfunction "C_3") (pintype "passive"))
      (node (ref "Q3") (pin "1") (pinfunction "B_1") (pintype "passive"))
      (node (ref "R196") (pin "2") (pinfunction "2_2") (pintype "passive"))
    )
    (net (code "43") (name "Net-(Q2-E)") (class "Default")
      (node (ref "Q2") (pin "2") (pinfunction "E_2") (pintype "passive"))
      (node (ref "U27") (pin "1") (pinfunction "DRV2_1") (pintype "passive"))
    )
    (net (code "44") (name "Net-(Q4-C)") (class "Default")
      (node (ref "Q4") (pin "3") (pinfunction "C_3") (pintype "passive"))
      (node (ref "Q5") (pin "1") (pinfunction "B_1") (pintype "passive"))
      (node (ref "R201") (pin "2") (pinfunction "2_2") (pintype "passive"))
    )
    (net (code "45") (name "Net-(Q4-E)") (class "Default")
      (node (ref "Q4") (pin "2") (pinfunction "E_2") (pintype "passive"))
      (node (ref "U27") (pin "4") (pinfunction "DRV3_4") (pintype "passive"))
    )
    (net (code "46") (name "Net-(Q6-C)") (class "Default")
      (node (ref "Q6") (pin "3") (pinfunction "C_3") (pintype "passive"))
      (node (ref "Q7") (pin "1") (pinfunction "B_1") (pintype "passive"))
      (node (ref "R216") (pin "2") (pinfunction "2_2") (pintype "passive"))
    )
    (net (code "47") (name "Net-(Q6-E)") (class "Default")
      (node (ref "Q6") (pin "2") (pinfunction "E_2") (pintype "passive"))
      (node (ref "U27") (pin "10") (pinfunction "DRV5_10") (pintype "passive"))
    )
    (net (code "48") (name "Net-(Q8-B)") (class "Default")
      (node (ref "Q8") (pin "1") (pinfunction "B_1") (pintype "passive"))
      (node (ref "R217") (pin "2") (pinfunction "2_2") (pintype "passive"))
      (node (ref "U27") (pin "8") (pinfunction "DRV4_8") (pintype "passive"))
    )
    (net (code "49") (name "Net-(Q8-E)") (class "Default")
      (node (ref "C296") (pin "1") (pinfunction "1_1") (pintype "passive"))
      (node (ref "Q8") (pin "2") (pinfunction "E_2") (pintype "passive"))
      (node (ref "R212") (pin "2") (pinfunction "2_2") (pintype "passive"))
      (node (ref "R214") (pin "1") (pinfunction "1_1") (pintype "passive"))
      (node (ref "R217") (pin "1") (pinfunction "1_1") (pintype "passive"))
    )
    (net (code "50") (name "Net-(U27-BST)") (class "Default")
      (node (ref "R178") (pin "2") (pinfunction "2_2") (pintype "passive"))
      (node (ref "U27") (pin "24") (pinfunction "BST_24") (pintype "passive"))
    )
    (net (code "51") (name "Net-(U27-COMP)") (class "Default")
      (node (ref "R194") (pin "1") (pinfunction "1_1") (pintype "passive"))
      (node (ref "U27") (pin "13") (pinfunction "COMP_13") (pintype "input"))
    )
    (net (code "52") (name "Net-(U27-CSH)") (class "Default")
      (node (ref "R206") (pin "1") (pinfunction "1_1") (pintype "passive"))
      (node (ref "R210") (pin "2") (pinfunction "2_2") (pintype "passive"))
      (node (ref "R211") (pin "2") (pinfunction "2_2") (pintype "passive"))
      (node (ref "U27") (pin "5") (pinfunction "CSH_5") (pintype "input"))
    )
    (net (code "53") (name "Net-(U27-CSL)") (class "Default")
      (node (ref "R211") (pin "1") (pinfunction "1_1") (pintype "passive"))
      (node (ref "R214") (pin "2") (pinfunction "2_2") (pintype "passive"))
      (node (ref "U27") (pin "6") (pinfunction "CSL_6") (pintype "input"))
    )
    (net (code "54") (name "Net-(U27-DH)") (class "Default")
      (node (ref "R179") (pin "1") (pinfunction "1_1") (pintype "passive"))
      (node (ref "U27") (pin "23") (pinfunction "DH_23") (pintype "output"))
    )
    (net (code "55") (name "Net-(U27-DL)") (class "Default")
      (node (ref "D9") (pin "K") (pinfunction "K_K") (pintype "passive"))
      (node (ref "R191") (pin "1") (pinfunction "1_1") (pintype "passive"))
      (node (ref "U27") (pin "21") (pinfunction "DL_21") (pintype "output"))
    )
    (net (code "56") (name "Net-(U27-FB)") (class "Default")
      (node (ref "C276") (pin "2") (pinfunction "2_2") (pintype "passive"))
      (node (ref "R187") (pin "2") (pinfunction "2_2") (pintype "passive"))
      (node (ref "R190") (pin "1") (pinfunction "1_1") (pintype "passive"))
      (node (ref "U27") (pin "11") (pinfunction "RSTIN_11") (pintype "input"))
      (node (ref "U27") (pin "14") (pinfunction "FB_14") (pintype "input"))
    )
    (net (code "57") (name "Net-(U27-FBL1)") (class "Default")
      (node (ref "R337") (pin "2") (pinfunction "2_2") (pintype "passive"))
      (node (ref "R338") (pin "1") (pinfunction "1_1") (pintype "passive"))
      (node (ref "U27") (pin "31") (pinfunction "FBL1_31") (pintype "input"))
    )
    (net (code "58") (name "Net-(U27-FBL2)") (class "Default")
      (node (ref "R202") (pin "2") (pinfunction "2_2") (pintype "passive"))
      (node (ref "R203") (pin "1") (pinfunction "1_1") (pintype "passive"))
      (node (ref "U27") (pin "2") (pinfunction "FBL2_2") (pintype "input"))
    )
    (net (code "59") (name "Net-(U27-FBL3)") (class "Default")
      (node (ref "R205") (pin "1") (pinfunction "1_1") (pintype "passive"))
      (node (ref "R207") (pin "1") (pinfunction "1_1") (pintype "passive"))
      (node (ref "U27") (pin "3") (pinfunction "FBL3_3") (pintype "input"))
    )
    (net (code "60") (name "Net-(U27-FBL4)") (class "Default")
      (node (ref "R220") (pin "2") (pinfunction "2_2") (pintype "passive"))
      (node (ref "R222") (pin "1") (pinfunction "1_1") (pintype "passive"))
      (node (ref "R224") (pin "1") (pinfunction "1_1") (pintype "passive"))
      (node (ref "U27") (pin "7") (pinfunction "FBL4_7") (pintype "input"))
    )
    (net (code "61") (name "Net-(U27-FBL5)") (class "Default")
      (node (ref "R221") (pin "1") (pinfunction "1_1") (pintype "passive"))
      (node (ref "R223") (pin "1") (pinfunction "1_1") (pintype "passive"))
      (node (ref "U27") (pin "9") (pinfunction "FBL5_9") (pintype "input"))
    )
    (net (code "62") (name "Net-(U27-ILIM)") (class "Default")
      (node (ref "R197") (pin "2") (pinfunction "2_2") (pintype "passive"))
      (node (ref "R199") (pin "1") (pinfunction "1_1") (pintype "passive"))
      (node (ref "U27") (pin "15") (pinfunction "ILIM_15") (pintype "input"))
    )
    (net (code "63") (name "Net-(U27-IN)") (class "Default")
      (node (ref "C271") (pin "1") (pinfunction "1_1") (pintype "passive"))
      (node (ref "R176") (pin "2") (pinfunction "2_2") (pintype "passive"))
      (node (ref "U27") (pin "27") (pinfunction "IN_27") (pintype "power_in"))
    )
    (net (code "64") (name "VCOM") (class "Default")
      (node (ref "C301") (pin "1") (pinfunction "1_1") (pintype "passive"))
      (node (ref "Q8") (pin "3") (pinfunction "C_3") (pintype "passive"))
      (node (ref "R220") (pin "1") (pinfunction "1_1") (pintype "passive"))
      (node (ref "TP13") (pin "1") (pinfunction "1_1") (pintype "passive"))
    )
    (net (code "65") (name "VDD") (class "Default")
      (node (ref "C275") (pin "1") (pinfunction "1_1") (pintype "passive"))
      (node (ref "FB10") (pin "2") (pinfunction "2_2") (pintype "passive"))
      (node (ref "R336") (pin "1") (pinfunction "1_1") (pintype "passive"))
      (node (ref "TP4") (pin "1") (pinfunction "1_1") (pintype "passive"))
    )
    (net (code "66") (name "VGH") (class "Default")
      (node (ref "C289") (pin "1") (pinfunction "1_1") (pintype "passive"))
      (node (ref "Q5") (pin "3") (pinfunction "C_3") (pintype "passive"))
      (node (ref "R205") (pin "2") (pinfunction "2_2") (pintype "passive"))
      (node (ref "TP11") (pin "1") (pinfunction "1_1") (pintype "passive"))
    )
    (net (code "67") (name "VGL") (class "Default")
      (node (ref "C302") (pin "1") (pinfunction "1_1") (pintype "passive"))
      (node (ref "D25") (pin "A") (pinfunction "A_A") (pintype "passive"))
      (node (ref "Q7") (pin "3") (pinfunction "C_3") (pintype "passive"))
      (node (ref "R221") (pin "2") (pinfunction "2_2") (pintype "passive"))
      (node (ref "TP12") (pin "1") (pinfunction "1_1") (pintype "passive"))
    )
    (net (code "68") (name "VL") (class "Default")
      (node (ref "C272") (pin "1") (pinfunction "1_1") (pintype "passive"))
      (node (ref "D8") (pin "A") (pinfunction "A_A") (pintype "passive"))
      (node (ref "R197") (pin "1") (pinfunction "1_1") (pintype "passive"))
      (node (ref "R206") (pin "2") (pinfunction "2_2") (pintype "passive"))
      (node (ref "R223") (pin "2") (pinfunction "2_2") (pintype "passive"))
      (node (ref "R337") (pin "1") (pinfunction "1_1") (pintype "passive"))
      (node (ref "TP14") (pin "1") (pinfunction "1_1") (pintype "passive"))
      (node (ref "U27") (pin "25") (pinfunction "SEQ_25") (pintype "input"))
      (node (ref "U27") (pin "26") (pinfunction "FREQ_26") (pintype "input"))
      (node (ref "U27") (pin "28") (pinfunction "VL_28") (pintype "output"))
    )
    (net (code "69") (name "V_MAX1531") (class "Default")
      (node (ref "C268") (pin "1") (pinfunction "1_1") (pintype "passive"))
      (node (ref "D12") (pin "3") (pinfunction "A1_3") (pintype "passive"))
      (node (ref "FB31") (pin "2") (pinfunction "2_2") (pintype "passive"))
      (node (ref "Q1") (pin "7") (pinfunction "D1_7") (pintype "passive"))
      (node (ref "Q1") (pin "8") (pinfunction "D1_8") (pintype "passive"))
      (node (ref "Q2") (pin "1") (pinfunction "B_1") (pintype "passive"))
      (node (ref "Q4") (pin "1") (pinfunction "B_1") (pintype "passive"))
      (node (ref "R176") (pin "1") (pinfunction "1_1") (pintype "passive"))
      (node (ref "R210") (pin "1") (pinfunction "1_1") (pintype "passive"))
      (node (ref "R212") (pin "1") (pinfunction "1_1") (pintype "passive"))
      (node (ref "TP16") (pin "1") (pinfunction "1_1") (pintype "passive"))
    )
    (net (code "70") (name "V_NEG") (class "Default")
      (node (ref "C294") (pin "1") (pinfunction "1_1") (pintype "passive"))
      (node (ref "D10") (pin "3") (pinfunction "A1_3") (pintype "passive"))
      (node (ref "Q7") (pin "2") (pinfunction "E_2") (pintype "passive"))
      (node (ref "R216") (pin "1") (pinfunction "1_1") (pintype "passive"))
    )
    (net (code "71") (name "V_x2") (class "Default")
      (node (ref "C282") (pin "1") (pinfunction "1_1") (pintype "passive"))
      (node (ref "C284") (pin "1") (pinfunction "1_1") (pintype "passive"))
      (node (ref "C305") (pin "1") (pinfunction "1_1") (pintype "passive"))
      (node (ref "D12") (pin "2") (pinfunction "K2_2") (pintype "passive"))
      (node (ref "Q3") (pin "3") (pinfunction "E_3") (pintype "passive"))
      (node (ref "Q5") (pin "2") (pinfunction "E_2") (pintype "passive"))
      (node (ref "R196") (pin "1") (pinfunction "1_1") (pintype "passive"))
      (node (ref "R201") (pin "1") (pinfunction "1_1") (pintype "passive"))
      (node (ref "TP15") (pin "1") (pinfunction "1_1") (pintype "passive"))
    )
    (net (code "72") (name "unconnected-(U27-DRV1-Pad32)") (class "Default")
      (node (ref "U27") (pin "32") (pinfunction "DRV1_32") (pintype "passive+no_connect"))
    )
  )
)
